# TTR1_Gr4_-_SIMON_Timoth_e_Pic.net
KiCad netlist of a schematic drawn in EAGLE
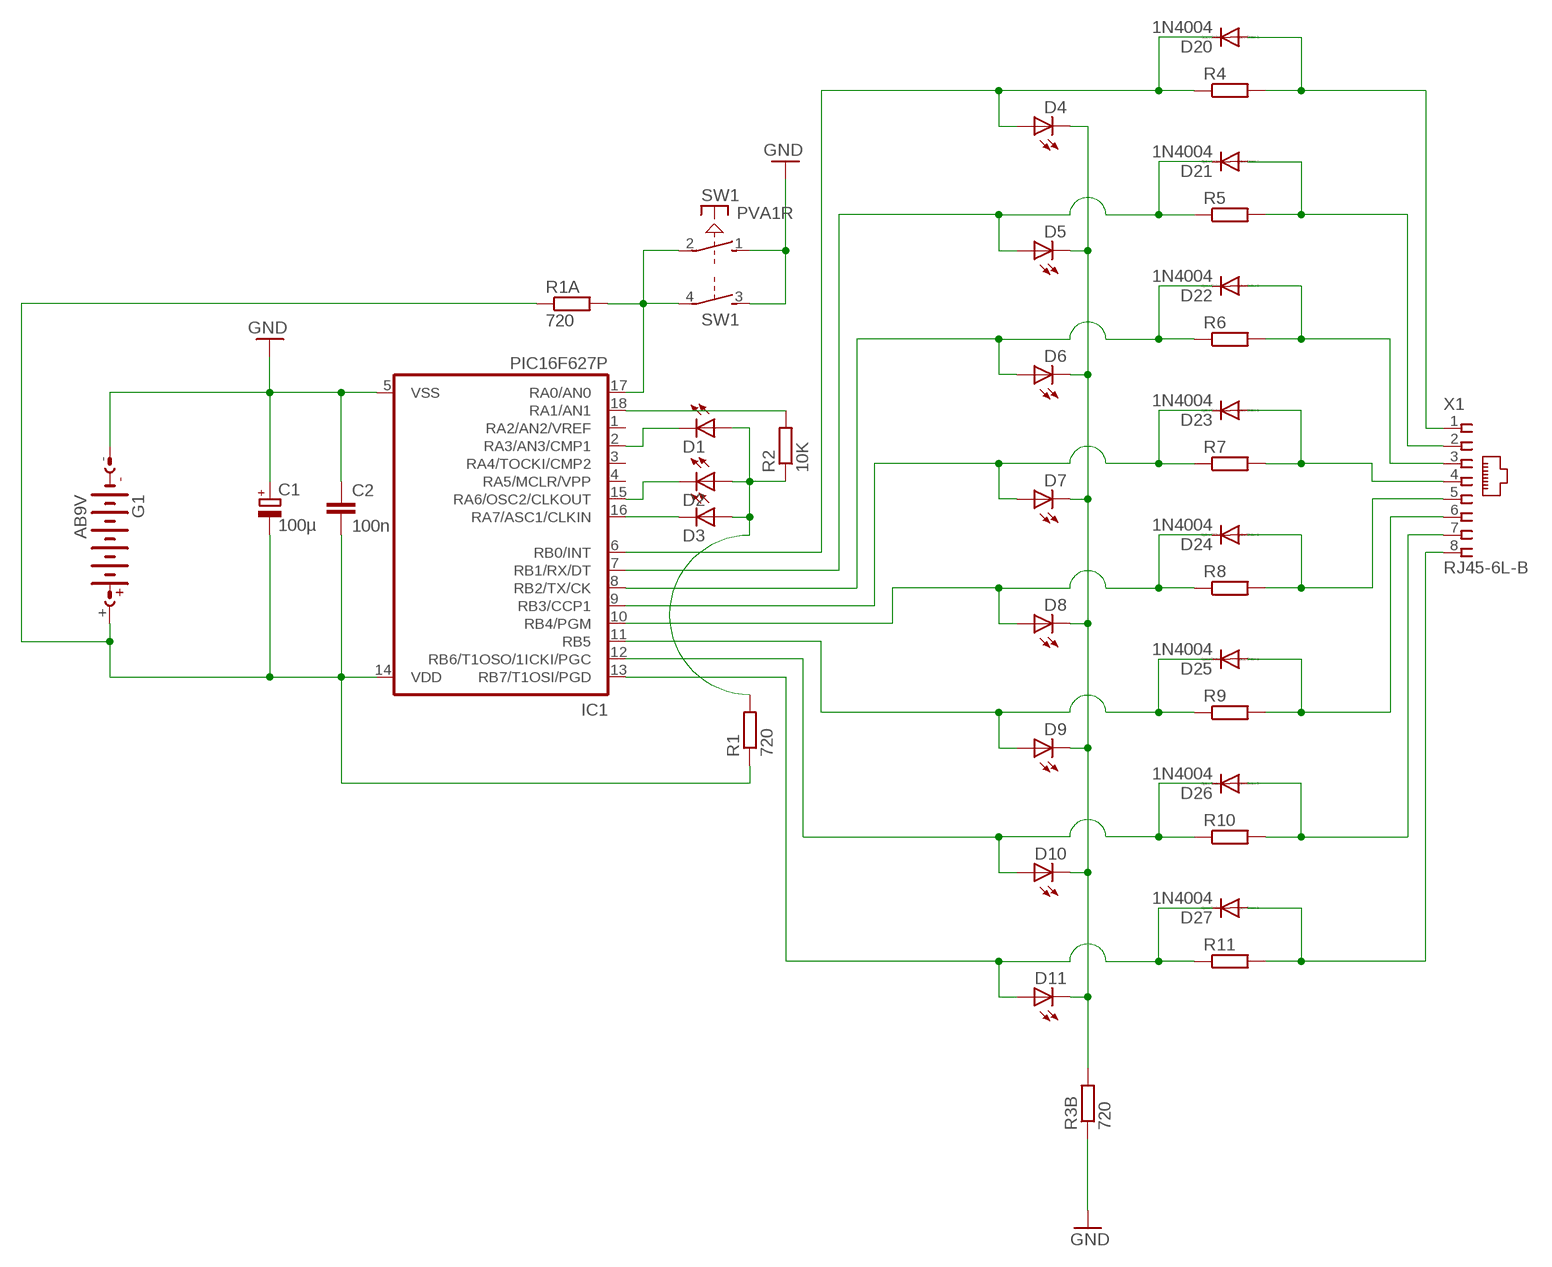
[diagram p0: schematic, sheet 1]

(export (version "E")
  (design (tool "Eeschema 10.0.6"))
  (components
    (comp (ref "C1")
      (value "100µ")
      (footprint "eagle-import:E5-6")
      (libsource (lib "eagle-import") (part "CPOL-EUE5-6"))
    )
    (comp (ref "C2")
      (value "100n")
      (footprint "eagle-import:C050-024X044")
      (libsource (lib "eagle-import") (part "C-EU050-024X044"))
    )
    (comp (ref "D1")
      (value "LED5MM")
      (footprint "eagle-import:LED5MM")
      (libsource (lib "eagle-import") (part "LED5MM"))
    )
    (comp (ref "D2")
      (value "LED5MM")
      (footprint "eagle-import:LED5MM")
      (libsource (lib "eagle-import") (part "LED5MM"))
    )
    (comp (ref "D3")
      (value "LED5MM")
      (footprint "eagle-import:LED5MM")
      (libsource (lib "eagle-import") (part "LED5MM"))
    )
    (comp (ref "D4")
      (value "LED5MM")
      (footprint "eagle-import:LED5MM")
      (libsource (lib "eagle-import") (part "LED5MM"))
    )
    (comp (ref "D5")
      (value "LED5MM")
      (footprint "eagle-import:LED5MM")
      (libsource (lib "eagle-import") (part "LED5MM"))
    )
    (comp (ref "D6")
      (value "LED5MM")
      (footprint "eagle-import:LED5MM")
      (libsource (lib "eagle-import") (part "LED5MM"))
    )
    (comp (ref "D7")
      (value "LED5MM")
      (footprint "eagle-import:LED5MM")
      (libsource (lib "eagle-import") (part "LED5MM"))
    )
    (comp (ref "D8")
      (value "LED5MM")
      (footprint "eagle-import:LED5MM")
      (libsource (lib "eagle-import") (part "LED5MM"))
    )
    (comp (ref "D9")
      (value "LED5MM")
      (footprint "eagle-import:LED5MM")
      (libsource (lib "eagle-import") (part "LED5MM"))
    )
    (comp (ref "D10")
      (value "LED5MM")
      (footprint "eagle-import:LED5MM")
      (libsource (lib "eagle-import") (part "LED5MM"))
    )
    (comp (ref "D11")
      (value "LED5MM")
      (footprint "eagle-import:LED5MM")
      (libsource (lib "eagle-import") (part "LED5MM"))
    )
    (comp (ref "D20")
      (value "1N4004")
      (footprint "eagle-import:DO41-10")
      (libsource (lib "eagle-import") (part "1N4004"))
    )
    (comp (ref "D21")
      (value "1N4004")
      (footprint "eagle-import:DO41-10")
      (libsource (lib "eagle-import") (part "1N4004"))
    )
    (comp (ref "D22")
      (value "1N4004")
      (footprint "eagle-import:DO41-10")
      (libsource (lib "eagle-import") (part "1N4004"))
    )
    (comp (ref "D23")
      (value "1N4004")
      (footprint "eagle-import:DO41-10")
      (libsource (lib "eagle-import") (part "1N4004"))
    )
    (comp (ref "D24")
      (value "1N4004")
      (footprint "eagle-import:DO41-10")
      (libsource (lib "eagle-import") (part "1N4004"))
    )
    (comp (ref "D25")
      (value "1N4004")
      (footprint "eagle-import:DO41-10")
      (libsource (lib "eagle-import") (part "1N4004"))
    )
    (comp (ref "D26")
      (value "1N4004")
      (footprint "eagle-import:DO41-10")
      (libsource (lib "eagle-import") (part "1N4004"))
    )
    (comp (ref "D27")
      (value "1N4004")
      (footprint "eagle-import:DO41-10")
      (libsource (lib "eagle-import") (part "1N4004"))
    )
    (comp (ref "G1")
      (value "AB9V")
      (footprint "eagle-import:AB9V")
      (libsource (lib "eagle-import") (part "AB9V"))
    )
    (comp (ref "IC1")
      (value "PIC16F627P")
      (footprint "eagle-import:DIL18")
      (fields (field (name "MF") "MICROCHIP") (field (name "MPN") "PIC16F627-20I/P"))
      (libsource (lib "eagle-import") (part "PIC16F627P"))
    )
    (comp (ref "R1")
      (value "720")
      (footprint "eagle-import:0204_7")
      (libsource (lib "eagle-import") (part "R-EU_0204/7"))
    )
    (comp (ref "R1A")
      (value "720")
      (footprint "eagle-import:0204_7")
      (libsource (lib "eagle-import") (part "R-EU_0204/7"))
    )
    (comp (ref "R2")
      (value "10K")
      (footprint "eagle-import:0204_7")
      (libsource (lib "eagle-import") (part "R-EU_0204/7"))
    )
    (comp (ref "R3B")
      (value "720")
      (footprint "eagle-import:0204_7")
      (libsource (lib "eagle-import") (part "R-EU_0204/7"))
    )
    (comp (ref "R4")
      (value "R-EU_0204/7")
      (footprint "eagle-import:0204_7")
      (libsource (lib "eagle-import") (part "R-EU_0204/7"))
    )
    (comp (ref "R5")
      (value "R-EU_0204/7")
      (footprint "eagle-import:0204_7")
      (libsource (lib "eagle-import") (part "R-EU_0204/7"))
    )
    (comp (ref "R6")
      (value "R-EU_0204/7")
      (footprint "eagle-import:0204_7")
      (libsource (lib "eagle-import") (part "R-EU_0204/7"))
    )
    (comp (ref "R7")
      (value "R-EU_0204/7")
      (footprint "eagle-import:0204_7")
      (libsource (lib "eagle-import") (part "R-EU_0204/7"))
    )
    (comp (ref "R8")
      (value "R-EU_0204/7")
      (footprint "eagle-import:0204_7")
      (libsource (lib "eagle-import") (part "R-EU_0204/7"))
    )
    (comp (ref "R9")
      (value "R-EU_0204/7")
      (footprint "eagle-import:0204_7")
      (libsource (lib "eagle-import") (part "R-EU_0204/7"))
    )
    (comp (ref "R10")
      (value "R-EU_0204/7")
      (footprint "eagle-import:0204_7")
      (libsource (lib "eagle-import") (part "R-EU_0204/7"))
    )
    (comp (ref "R11")
      (value "R-EU_0204/7")
      (footprint "eagle-import:0204_7")
      (libsource (lib "eagle-import") (part "R-EU_0204/7"))
    )
    (comp (ref "SW1")
      (value "PVA1R")
      (footprint "eagle-import:PVA1R")
      (libsource (lib "eagle-import") (part "PVA1R"))
    )
    (comp (ref "X1")
      (value "RJ45-6L-B")
      (footprint "eagle-import:RJ45-NO-SHIELD")
      (libsource (lib "eagle-import") (part "RJ45-6L-B"))
    )
  )
  (nets
    (net (code "1") (name "GND") (class "Default")
      (node (ref "C1") (pin "+") (pinfunction "+_+") (pintype "passive"))
      (node (ref "C2") (pin "1") (pinfunction "1_1") (pintype "passive"))
      (node (ref "G1") (pin "-") (pinfunction "-_-") (pintype "passive"))
      (node (ref "IC1") (pin "5") (pinfunction "VSS_5") (pintype "power_in"))
      (node (ref "R3B") (pin "1") (pinfunction "1_1") (pintype "passive"))
      (node (ref "SW1") (pin "1") (pinfunction "S_1") (pintype "passive"))
      (node (ref "SW1") (pin "3") (pinfunction "S_3") (pintype "passive"))
    )
    (net (code "2") (name "Net-(D1-C)") (class "Default")
      (node (ref "D1") (pin "K") (pinfunction "C_K") (pintype "passive"))
      (node (ref "IC1") (pin "2") (pinfunction "RA3/AN3/CMP1_2") (pintype "bidirectional"))
    )
    (net (code "3") (name "Net-(D1-PadA)") (class "Default")
      (node (ref "D1") (pin "A") (pinfunction "A_A") (pintype "passive"))
      (node (ref "D2") (pin "A") (pinfunction "A_A") (pintype "passive"))
      (node (ref "D3") (pin "A") (pinfunction "A_A") (pintype "passive"))
      (node (ref "R1") (pin "2") (pinfunction "2_2") (pintype "passive"))
      (node (ref "R2") (pin "1") (pinfunction "1_1") (pintype "passive"))
    )
    (net (code "4") (name "Net-(D2-C)") (class "Default")
      (node (ref "D2") (pin "K") (pinfunction "C_K") (pintype "passive"))
      (node (ref "IC1") (pin "15") (pinfunction "RA6/OSC2/CLKOUT_15") (pintype "bidirectional"))
    )
    (net (code "5") (name "Net-(D3-C)") (class "Default")
      (node (ref "D3") (pin "K") (pinfunction "C_K") (pintype "passive"))
      (node (ref "IC1") (pin "16") (pinfunction "RA7/ASC1/CLKIN_16") (pintype "bidirectional"))
    )
    (net (code "6") (name "Net-(D10-C)") (class "Default")
      (node (ref "D10") (pin "K") (pinfunction "C_K") (pintype "passive"))
      (node (ref "D11") (pin "K") (pinfunction "C_K") (pintype "passive"))
      (node (ref "D4") (pin "K") (pinfunction "C_K") (pintype "passive"))
      (node (ref "D5") (pin "K") (pinfunction "C_K") (pintype "passive"))
      (node (ref "D6") (pin "K") (pinfunction "C_K") (pintype "passive"))
      (node (ref "D7") (pin "K") (pinfunction "C_K") (pintype "passive"))
      (node (ref "D8") (pin "K") (pinfunction "C_K") (pintype "passive"))
      (node (ref "D9") (pin "K") (pinfunction "C_K") (pintype "passive"))
      (node (ref "R3B") (pin "2") (pinfunction "2_2") (pintype "passive"))
    )
    (net (code "7") (name "Net-(D20-PadA)") (class "Default")
      (node (ref "D20") (pin "A") (pinfunction "A_A") (pintype "passive"))
      (node (ref "R4") (pin "2") (pinfunction "2_2") (pintype "passive"))
      (node (ref "X1") (pin "1") (pinfunction "1_1") (pintype "passive"))
    )
    (net (code "8") (name "Net-(D21-PadA)") (class "Default")
      (node (ref "D21") (pin "A") (pinfunction "A_A") (pintype "passive"))
      (node (ref "R5") (pin "2") (pinfunction "2_2") (pintype "passive"))
      (node (ref "X1") (pin "2") (pinfunction "2_2") (pintype "passive"))
    )
    (net (code "9") (name "Net-(D22-PadA)") (class "Default")
      (node (ref "D22") (pin "A") (pinfunction "A_A") (pintype "passive"))
      (node (ref "R6") (pin "2") (pinfunction "2_2") (pintype "passive"))
      (node (ref "X1") (pin "3") (pinfunction "3_3") (pintype "passive"))
    )
    (net (code "10") (name "Net-(D23-PadA)") (class "Default")
      (node (ref "D23") (pin "A") (pinfunction "A_A") (pintype "passive"))
      (node (ref "R7") (pin "2") (pinfunction "2_2") (pintype "passive"))
      (node (ref "X1") (pin "4") (pinfunction "4_4") (pintype "passive"))
    )
    (net (code "11") (name "Net-(D24-PadA)") (class "Default")
      (node (ref "D24") (pin "A") (pinfunction "A_A") (pintype "passive"))
      (node (ref "R8") (pin "2") (pinfunction "2_2") (pintype "passive"))
      (node (ref "X1") (pin "5") (pinfunction "5_5") (pintype "passive"))
    )
    (net (code "12") (name "Net-(D25-PadA)") (class "Default")
      (node (ref "D25") (pin "A") (pinfunction "A_A") (pintype "passive"))
      (node (ref "R9") (pin "2") (pinfunction "2_2") (pintype "passive"))
      (node (ref "X1") (pin "6") (pinfunction "6_6") (pintype "passive"))
    )
    (net (code "13") (name "Net-(D26-PadA)") (class "Default")
      (node (ref "D26") (pin "A") (pinfunction "A_A") (pintype "passive"))
      (node (ref "R10") (pin "2") (pinfunction "2_2") (pintype "passive"))
      (node (ref "X1") (pin "7") (pinfunction "7_7") (pintype "passive"))
    )
    (net (code "14") (name "Net-(D27-PadA)") (class "Default")
      (node (ref "D27") (pin "A") (pinfunction "A_A") (pintype "passive"))
      (node (ref "R11") (pin "2") (pinfunction "2_2") (pintype "passive"))
      (node (ref "X1") (pin "8") (pinfunction "8_8") (pintype "passive"))
    )
    (net (code "15") (name "Net-(IC1-RA0{slash}AN0)") (class "Default")
      (node (ref "IC1") (pin "17") (pinfunction "RA0/AN0_17") (pintype "bidirectional"))
      (node (ref "R1A") (pin "2") (pinfunction "2_2") (pintype "passive"))
      (node (ref "SW1") (pin "2") (pinfunction "P_2") (pintype "passive"))
      (node (ref "SW1") (pin "4") (pinfunction "P_4") (pintype "passive"))
    )
    (net (code "16") (name "Net-(IC1-RA1{slash}AN1)") (class "Default")
      (node (ref "IC1") (pin "18") (pinfunction "RA1/AN1_18") (pintype "bidirectional"))
      (node (ref "R2") (pin "2") (pinfunction "2_2") (pintype "passive"))
    )
    (net (code "17") (name "Net-(IC1-RB0{slash}INT)") (class "Default")
      (node (ref "D20") (pin "C") (pinfunction "C_C") (pintype "passive"))
      (node (ref "D4") (pin "A") (pinfunction "A_A") (pintype "passive"))
      (node (ref "IC1") (pin "6") (pinfunction "RB0/INT_6") (pintype "bidirectional"))
      (node (ref "R4") (pin "1") (pinfunction "1_1") (pintype "passive"))
    )
    (net (code "18") (name "Net-(IC1-RB1{slash}RX{slash}DT)") (class "Default")
      (node (ref "D21") (pin "C") (pinfunction "C_C") (pintype "passive"))
      (node (ref "D5") (pin "A") (pinfunction "A_A") (pintype "passive"))
      (node (ref "IC1") (pin "7") (pinfunction "RB1/RX/DT_7") (pintype "bidirectional"))
      (node (ref "R5") (pin "1") (pinfunction "1_1") (pintype "passive"))
    )
    (net (code "19") (name "Net-(IC1-RB2{slash}TX{slash}CK)") (class "Default")
      (node (ref "D22") (pin "C") (pinfunction "C_C") (pintype "passive"))
      (node (ref "D6") (pin "A") (pinfunction "A_A") (pintype "passive"))
      (node (ref "IC1") (pin "8") (pinfunction "RB2/TX/CK_8") (pintype "bidirectional"))
      (node (ref "R6") (pin "1") (pinfunction "1_1") (pintype "passive"))
    )
    (net (code "20") (name "Net-(IC1-RB3{slash}CCP1)") (class "Default")
      (node (ref "D23") (pin "C") (pinfunction "C_C") (pintype "passive"))
      (node (ref "D7") (pin "A") (pinfunction "A_A") (pintype "passive"))
      (node (ref "IC1") (pin "9") (pinfunction "RB3/CCP1_9") (pintype "bidirectional"))
      (node (ref "R7") (pin "1") (pinfunction "1_1") (pintype "passive"))
    )
    (net (code "21") (name "Net-(IC1-RB4{slash}PGM)") (class "Default")
      (node (ref "D24") (pin "C") (pinfunction "C_C") (pintype "passive"))
      (node (ref "D8") (pin "A") (pinfunction "A_A") (pintype "passive"))
      (node (ref "IC1") (pin "10") (pinfunction "RB4/PGM_10") (pintype "bidirectional"))
      (node (ref "R8") (pin "1") (pinfunction "1_1") (pintype "passive"))
    )
    (net (code "22") (name "Net-(IC1-RB5)") (class "Default")
      (node (ref "D25") (pin "C") (pinfunction "C_C") (pintype "passive"))
      (node (ref "D9") (pin "A") (pinfunction "A_A") (pintype "passive"))
      (node (ref "IC1") (pin "11") (pinfunction "RB5_11") (pintype "bidirectional"))
      (node (ref "R9") (pin "1") (pinfunction "1_1") (pintype "passive"))
    )
    (net (code "23") (name "Net-(IC1-RB6{slash}T1OSO{slash}1ICKI{slash}PGC)") (class "Default")
      (node (ref "D10") (pin "A") (pinfunction "A_A") (pintype "passive"))
      (node (ref "D26") (pin "C") (pinfunction "C_C") (pintype "passive"))
      (node (ref "IC1") (pin "12") (pinfunction "RB6/T1OSO/1ICKI/PGC_12") (pintype "bidirectional"))
      (node (ref "R10") (pin "1") (pinfunction "1_1") (pintype "passive"))
    )
    (net (code "24") (name "Net-(IC1-RB7{slash}T1OSI{slash}PGD)") (class "Default")
      (node (ref "D11") (pin "A") (pinfunction "A_A") (pintype "passive"))
      (node (ref "D27") (pin "C") (pinfunction "C_C") (pintype "passive"))
      (node (ref "IC1") (pin "13") (pinfunction "RB7/T1OSI/PGD_13") (pintype "bidirectional"))
      (node (ref "R11") (pin "1") (pinfunction "1_1") (pintype "passive"))
    )
    (net (code "25") (name "Net-(IC1-VDD)") (class "Default")
      (node (ref "C1") (pin "-") (pinfunction "-_-") (pintype "passive"))
      (node (ref "C2") (pin "2") (pinfunction "2_2") (pintype "passive"))
      (node (ref "G1") (pin "+") (pinfunction "+_+") (pintype "passive"))
      (node (ref "IC1") (pin "14") (pinfunction "VDD_14") (pintype "power_in"))
      (node (ref "R1") (pin "1") (pinfunction "1_1") (pintype "passive"))
      (node (ref "R1A") (pin "1") (pinfunction "1_1") (pintype "passive"))
    )
    (net (code "26") (name "unconnected-(IC1-RA2{slash}AN2{slash}VREF-Pad1)") (class "Default")
      (node (ref "IC1") (pin "1") (pinfunction "RA2/AN2/VREF_1") (pintype "bidirectional"))
    )
    (net (code "27") (name "unconnected-(IC1-RA4{slash}TOCKI{slash}CMP2-Pad3)") (class "Default")
      (node (ref "IC1") (pin "3") (pinfunction "RA4/TOCKI/CMP2_3") (pintype "bidirectional"))
    )
    (net (code "28") (name "unconnected-(IC1-RA5{slash}MCLR{slash}VPP-Pad4)") (class "Default")
      (node (ref "IC1") (pin "4") (pinfunction "RA5/MCLR/VPP_4") (pintype "input"))
    )
  )
)
